# 12_SHR_New.net
KiCad netlist of a schematic drawn in EAGLE
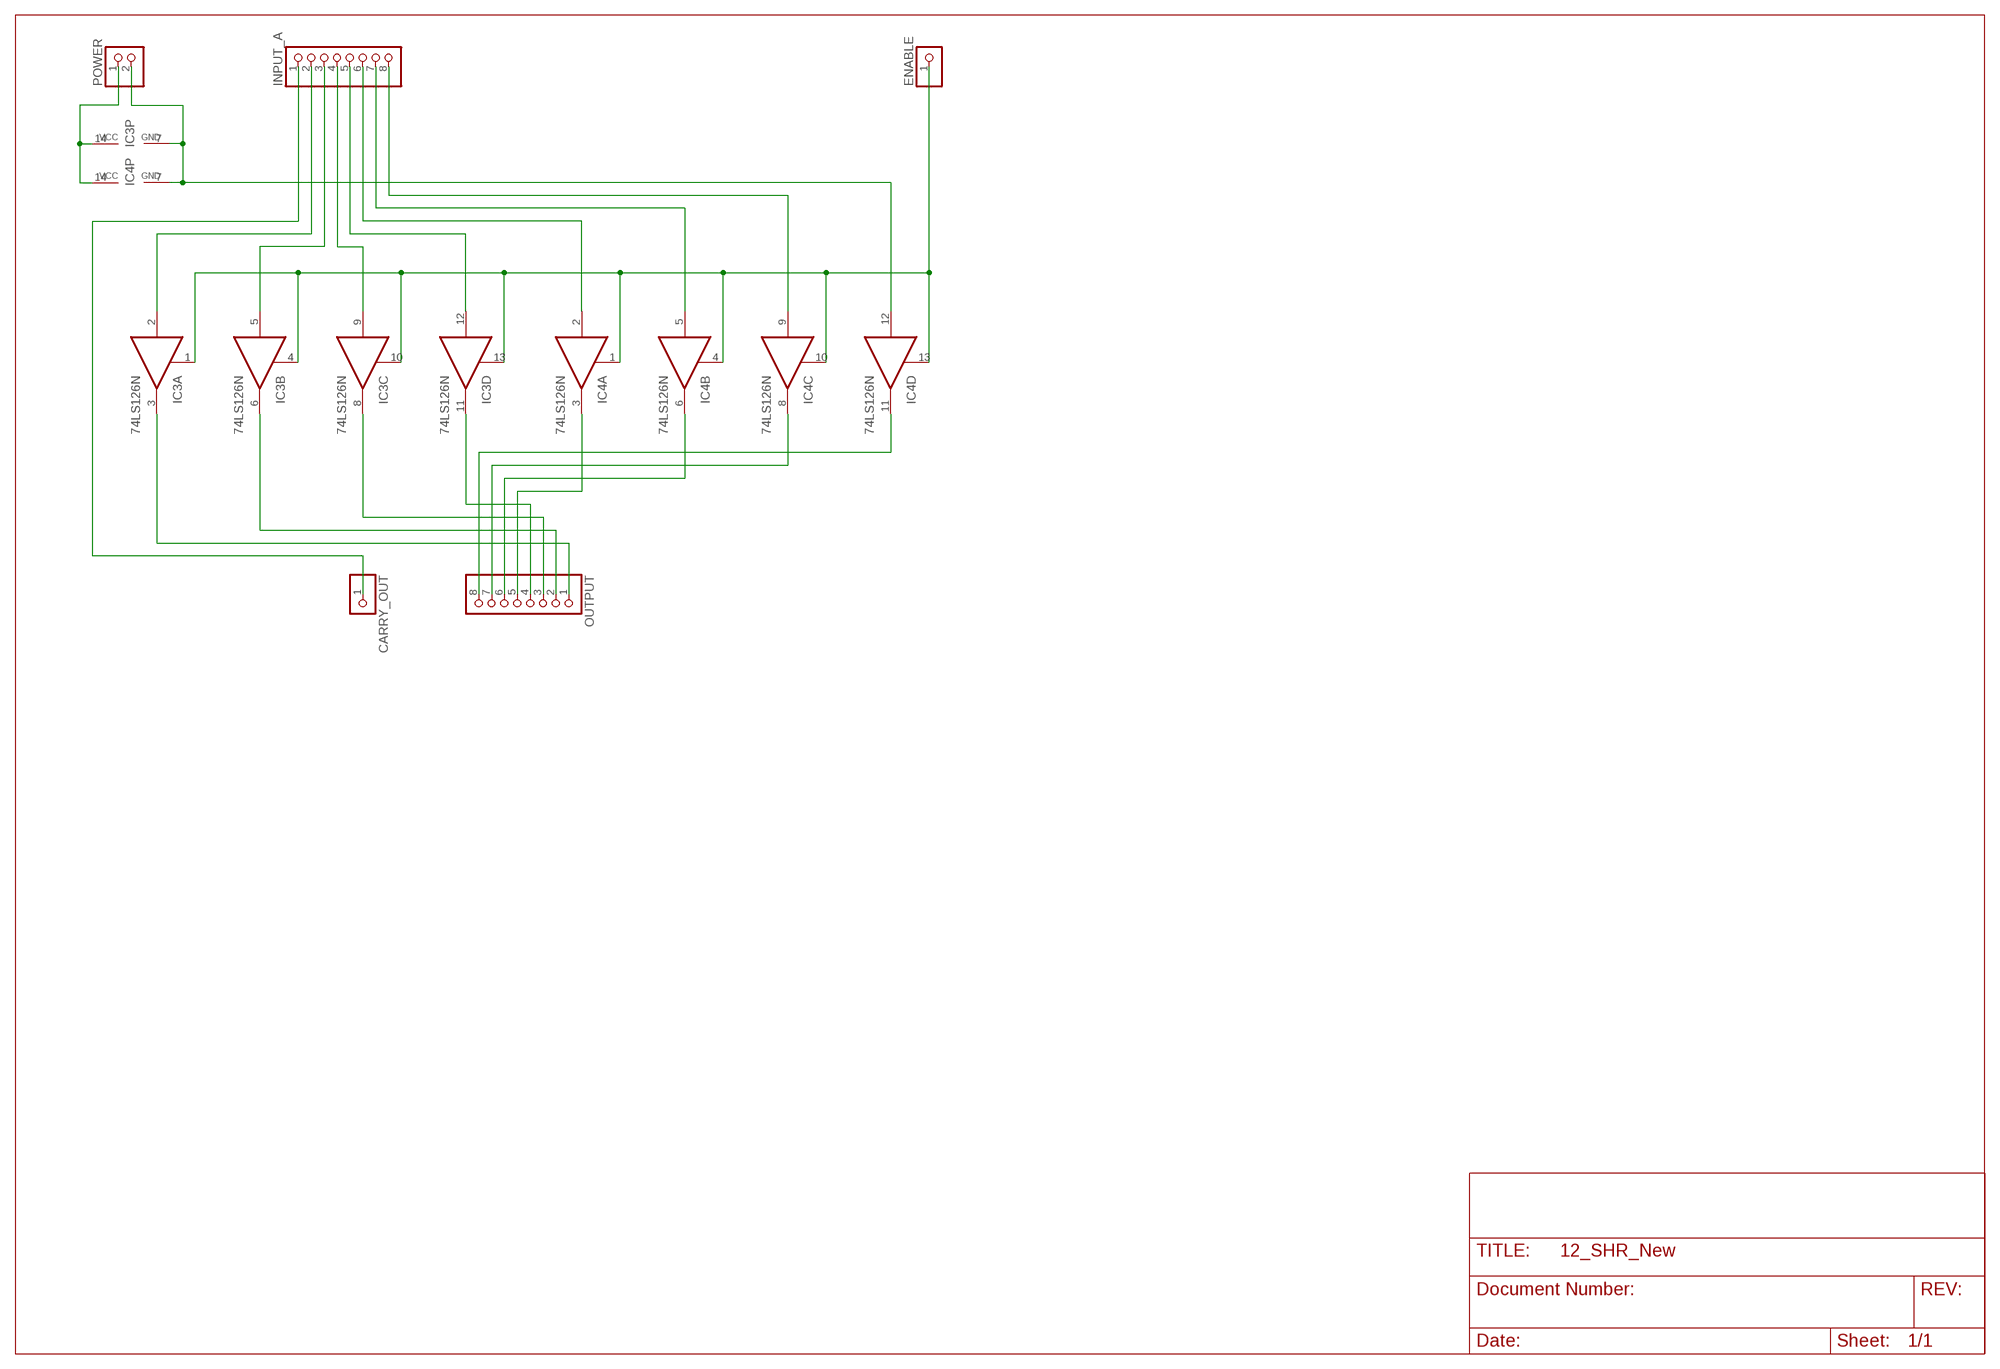
[diagram p0: schematic, sheet 1]

(export (version "E")
  (design (tool "Eeschema 10.0.6"))
  (components
    (comp (ref "CARRY_OUT")
      (value "PINHD-1X1")
      (footprint "eagle-import:1X01")
      (libsource (lib "eagle-import") (part "PINHD-1X1"))
    )
    (comp (ref "ENABLE")
      (value "PINHD-1X1")
      (footprint "eagle-import:1X01")
      (libsource (lib "eagle-import") (part "PINHD-1X1"))
    )
    (comp (ref "IC3")
      (value "74LS126N")
      (footprint "eagle-import:DIL14")
      (libsource (lib "eagle-import") (part "74126NLS"))
    )
    (comp (ref "IC4")
      (value "74LS126N")
      (footprint "eagle-import:DIL14")
      (libsource (lib "eagle-import") (part "74126NLS"))
    )
    (comp (ref "INPUT_A")
      (value "PINHD-1X8")
      (footprint "eagle-import:1X08")
      (libsource (lib "eagle-import") (part "PINHD-1X8"))
    )
    (comp (ref "OUTPUT")
      (value "PINHD-1X8")
      (footprint "eagle-import:1X08")
      (libsource (lib "eagle-import") (part "PINHD-1X8"))
    )
    (comp (ref "POWER")
      (value "PINHD-1X2")
      (footprint "eagle-import:1X02")
      (libsource (lib "eagle-import") (part "PINHD-1X2"))
    )
  )
  (nets
    (net (code "1") (name "Net-(CARRY_OUT-Pad1)") (class "Default")
      (node (ref "CARRY_OUT") (pin "1") (pinfunction "1_1") (pintype "passive"))
      (node (ref "INPUT_A") (pin "1") (pinfunction "1_1") (pintype "passive"))
    )
    (net (code "2") (name "Net-(IC3A-I)") (class "Default")
      (node (ref "IC3") (pin "2") (pinfunction "I_2") (pintype "input"))
      (node (ref "INPUT_A") (pin "2") (pinfunction "2_2") (pintype "passive"))
    )
    (net (code "3") (name "Net-(IC3A-O)") (class "Default")
      (node (ref "IC3") (pin "3") (pinfunction "O_3") (pintype "output"))
      (node (ref "OUTPUT") (pin "1") (pinfunction "1_1") (pintype "passive"))
    )
    (net (code "4") (name "Net-(IC3A-OE)") (class "Default")
      (node (ref "ENABLE") (pin "1") (pinfunction "1_1") (pintype "passive"))
      (node (ref "IC3") (pin "1") (pinfunction "OE_1") (pintype "input"))
      (node (ref "IC3") (pin "10") (pinfunction "OE_10") (pintype "input"))
      (node (ref "IC3") (pin "13") (pinfunction "OE_13") (pintype "input"))
      (node (ref "IC3") (pin "4") (pinfunction "OE_4") (pintype "input"))
      (node (ref "IC4") (pin "1") (pinfunction "OE_1") (pintype "input"))
      (node (ref "IC4") (pin "10") (pinfunction "OE_10") (pintype "input"))
      (node (ref "IC4") (pin "13") (pinfunction "OE_13") (pintype "input"))
      (node (ref "IC4") (pin "4") (pinfunction "OE_4") (pintype "input"))
    )
    (net (code "5") (name "Net-(IC3B-I)") (class "Default")
      (node (ref "IC3") (pin "5") (pinfunction "I_5") (pintype "input"))
      (node (ref "INPUT_A") (pin "3") (pinfunction "3_3") (pintype "passive"))
    )
    (net (code "6") (name "Net-(IC3B-O)") (class "Default")
      (node (ref "IC3") (pin "6") (pinfunction "O_6") (pintype "output"))
      (node (ref "OUTPUT") (pin "2") (pinfunction "2_2") (pintype "passive"))
    )
    (net (code "7") (name "Net-(IC3C-I)") (class "Default")
      (node (ref "IC3") (pin "9") (pinfunction "I_9") (pintype "input"))
      (node (ref "INPUT_A") (pin "4") (pinfunction "4_4") (pintype "passive"))
    )
    (net (code "8") (name "Net-(IC3C-O)") (class "Default")
      (node (ref "IC3") (pin "8") (pinfunction "O_8") (pintype "output"))
      (node (ref "OUTPUT") (pin "3") (pinfunction "3_3") (pintype "passive"))
    )
    (net (code "9") (name "Net-(IC3D-I)") (class "Default")
      (node (ref "IC3") (pin "12") (pinfunction "I_12") (pintype "input"))
      (node (ref "INPUT_A") (pin "5") (pinfunction "5_5") (pintype "passive"))
    )
    (net (code "10") (name "Net-(IC3D-O)") (class "Default")
      (node (ref "IC3") (pin "11") (pinfunction "O_11") (pintype "output"))
      (node (ref "OUTPUT") (pin "4") (pinfunction "4_4") (pintype "passive"))
    )
    (net (code "11") (name "Net-(IC3E-GND)") (class "Default")
      (node (ref "IC3") (pin "7") (pinfunction "GND_7") (pintype "power_in"))
      (node (ref "IC4") (pin "12") (pinfunction "I_12") (pintype "input"))
      (node (ref "IC4") (pin "7") (pinfunction "GND_7") (pintype "power_in"))
      (node (ref "POWER") (pin "2") (pinfunction "2_2") (pintype "passive"))
    )
    (net (code "12") (name "Net-(IC3E-VCC)") (class "Default")
      (node (ref "IC3") (pin "14") (pinfunction "VCC_14") (pintype "power_in"))
      (node (ref "IC4") (pin "14") (pinfunction "VCC_14") (pintype "power_in"))
      (node (ref "POWER") (pin "1") (pinfunction "1_1") (pintype "passive"))
    )
    (net (code "13") (name "Net-(IC4A-I)") (class "Default")
      (node (ref "IC4") (pin "2") (pinfunction "I_2") (pintype "input"))
      (node (ref "INPUT_A") (pin "6") (pinfunction "6_6") (pintype "passive"))
    )
    (net (code "14") (name "Net-(IC4A-O)") (class "Default")
      (node (ref "IC4") (pin "3") (pinfunction "O_3") (pintype "output"))
      (node (ref "OUTPUT") (pin "5") (pinfunction "5_5") (pintype "passive"))
    )
    (net (code "15") (name "Net-(IC4B-I)") (class "Default")
      (node (ref "IC4") (pin "5") (pinfunction "I_5") (pintype "input"))
      (node (ref "INPUT_A") (pin "7") (pinfunction "7_7") (pintype "passive"))
    )
    (net (code "16") (name "Net-(IC4B-O)") (class "Default")
      (node (ref "IC4") (pin "6") (pinfunction "O_6") (pintype "output"))
      (node (ref "OUTPUT") (pin "6") (pinfunction "6_6") (pintype "passive"))
    )
    (net (code "17") (name "Net-(IC4C-I)") (class "Default")
      (node (ref "IC4") (pin "9") (pinfunction "I_9") (pintype "input"))
      (node (ref "INPUT_A") (pin "8") (pinfunction "8_8") (pintype "passive"))
    )
    (net (code "18") (name "Net-(IC4C-O)") (class "Default")
      (node (ref "IC4") (pin "8") (pinfunction "O_8") (pintype "output"))
      (node (ref "OUTPUT") (pin "7") (pinfunction "7_7") (pintype "passive"))
    )
    (net (code "19") (name "Net-(IC4D-O)") (class "Default")
      (node (ref "IC4") (pin "11") (pinfunction "O_11") (pintype "output"))
      (node (ref "OUTPUT") (pin "8") (pinfunction "8_8") (pintype "passive"))
    )
  )
)
